# BigBoard.net
KiCad netlist of a schematic drawn in Altium Designer
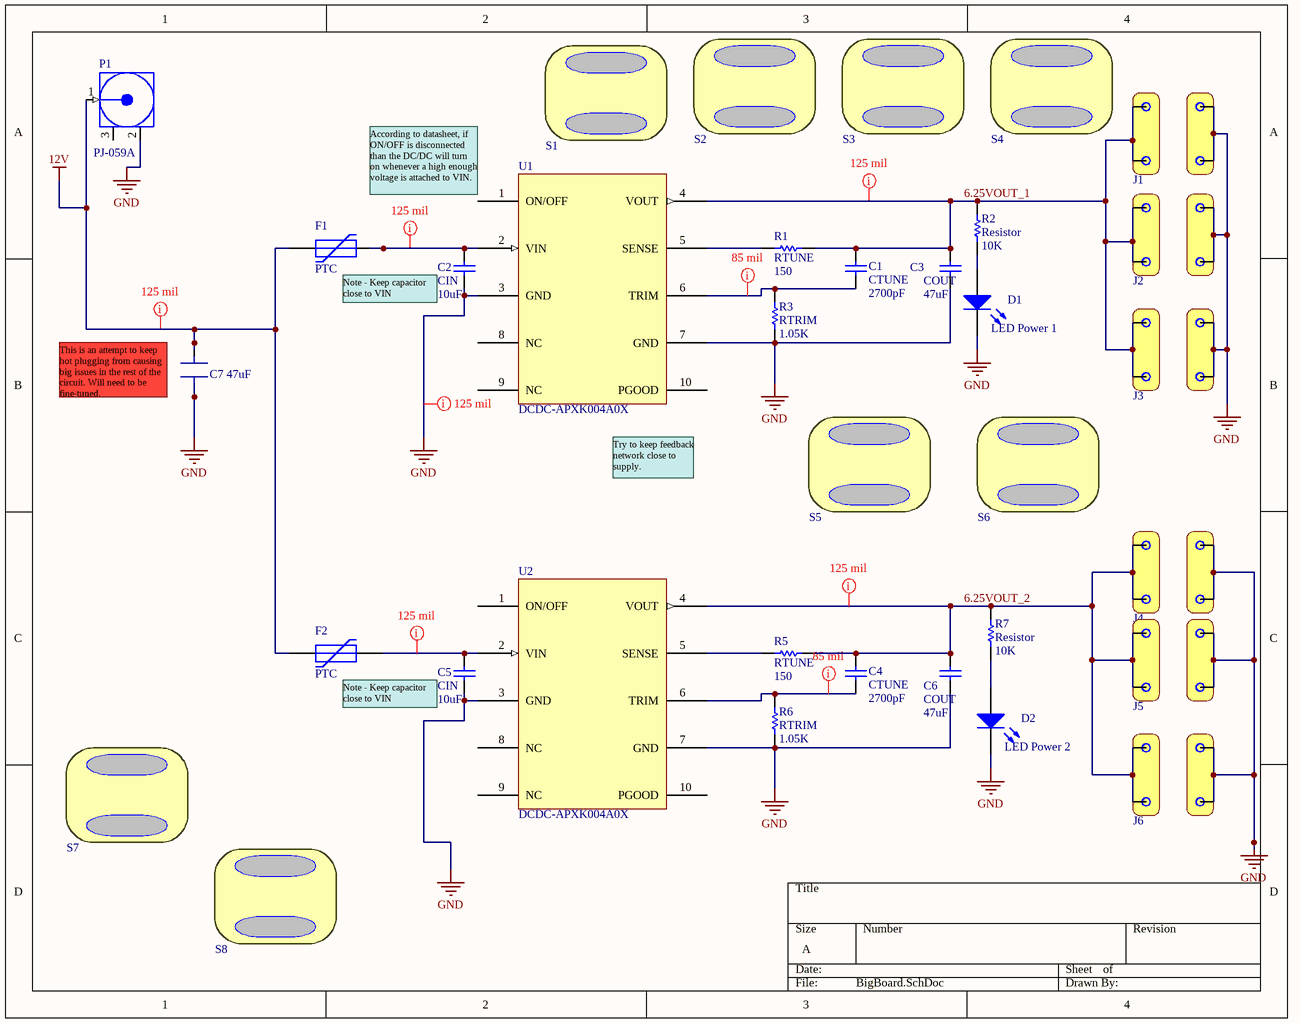
[diagram p0: BigBoard.SchDoc]

(export (version "E")
  (design (tool "Eeschema 10.0.6"))
  (components
    (comp (ref "C1")
      (value "CTUNE")
      (footprint "CAPC1608L")
      (description "Capacitor")
      (fields (field (name "ALTIUM_VALUE") "2700pF") (field (name "PUBLISHER") "Altium Limited"))
      (libsource (lib "mrone") (part "Cap"))
    )
    (comp (ref "C2")
      (value "CIN")
      (footprint "CAPC2012L")
      (description "Capacitor")
      (fields (field (name "ALTIUM_VALUE") "10uF") (field (name "PUBLISHER") "Altium Limited"))
      (libsource (lib "mrone") (part "Cap"))
    )
    (comp (ref "C3")
      (value "COUT")
      (footprint "CAPC3216L")
      (description "Capacitor")
      (fields (field (name "ALTIUM_VALUE") "47uF") (field (name "PUBLISHER") "Altium Limited"))
      (libsource (lib "mrone") (part "Cap"))
    )
    (comp (ref "C4")
      (value "CTUNE")
      (footprint "CAPC1608L")
      (description "Capacitor")
      (fields (field (name "ALTIUM_VALUE") "2700pF") (field (name "PUBLISHER") "Altium Limited"))
      (libsource (lib "mrone") (part "Cap"))
    )
    (comp (ref "C5")
      (value "CIN")
      (footprint "CAPC2012L")
      (description "Capacitor")
      (fields (field (name "ALTIUM_VALUE") "10uF") (field (name "PUBLISHER") "Altium Limited"))
      (libsource (lib "mrone") (part "Cap"))
    )
    (comp (ref "C6")
      (value "COUT")
      (footprint "CAPC3216L")
      (description "Capacitor")
      (fields (field (name "ALTIUM_VALUE") "47uF") (field (name "PUBLISHER") "Altium Limited"))
      (libsource (lib "mrone") (part "Cap"))
    )
    (comp (ref "C7 47uF")
      (value "CapTant6032-28")
      (footprint "CapTant6032-28")
      (description "Polarized Tantalum Capacitor for use in Toaster Charger")
      (libsource (lib "mrsl") (part "CapTant6032-28"))
    )
    (comp (ref "D1")
      (value "LED Power 1")
      (footprint "SurfaceMount(603)")
      (libsource (lib "mrone") (part "LED"))
    )
    (comp (ref "D2")
      (value "LED Power 2")
      (footprint "SurfaceMount(603)")
      (libsource (lib "mrone") (part "LED"))
    )
    (comp (ref "F1")
      (value "PTC")
      (footprint "J1-1812")
      (description "Fuse")
      (fields (field (name "PUBLISHER") "Altium Limited"))
      (libsource (lib "mrone") (part "PTC_FUSE"))
    )
    (comp (ref "F2")
      (value "PTC")
      (footprint "J1-1812")
      (description "Fuse")
      (fields (field (name "PUBLISHER") "Altium Limited"))
      (libsource (lib "mrone") (part "PTC_FUSE"))
    )
    (comp (ref "J1")
      (value "ToasterChargerProng")
      (footprint "ToasterChargerProng")
      (description "Charger Prong Footprint for Toaster Charger")
      (fields (field (name "PUBLISHER") "Altium Limited"))
      (libsource (lib "mrsl") (part "ToasterChargerProng"))
    )
    (comp (ref "J2")
      (value "ToasterChargerProng")
      (footprint "ToasterChargerProng")
      (description "Charger Prong Footprint for Toaster Charger")
      (fields (field (name "PUBLISHER") "Altium Limited"))
      (libsource (lib "mrsl") (part "ToasterChargerProng"))
    )
    (comp (ref "J3")
      (value "ToasterChargerProng")
      (footprint "ToasterChargerProng")
      (description "Charger Prong Footprint for Toaster Charger")
      (fields (field (name "PUBLISHER") "Altium Limited"))
      (libsource (lib "mrsl") (part "ToasterChargerProng"))
    )
    (comp (ref "J4")
      (value "ToasterChargerProng")
      (footprint "ToasterChargerProng")
      (description "Charger Prong Footprint for Toaster Charger")
      (fields (field (name "PUBLISHER") "Altium Limited"))
      (libsource (lib "mrsl") (part "ToasterChargerProng"))
    )
    (comp (ref "J5")
      (value "ToasterChargerProng")
      (footprint "ToasterChargerProng")
      (description "Charger Prong Footprint for Toaster Charger")
      (fields (field (name "PUBLISHER") "Altium Limited"))
      (libsource (lib "mrsl") (part "ToasterChargerProng"))
    )
    (comp (ref "J6")
      (value "ToasterChargerProng")
      (footprint "ToasterChargerProng")
      (description "Charger Prong Footprint for Toaster Charger")
      (fields (field (name "PUBLISHER") "Altium Limited"))
      (libsource (lib "mrsl") (part "ToasterChargerProng"))
    )
    (comp (ref "P1") (value "PJ-059A") (footprint "PJ-059A") (libsource (lib "mrsl") (part "PJ-059A")))
    (comp (ref "R1")
      (value "RTUNE")
      (footprint "J1-0603")
      (description "Resistor")
      (fields (field (name "ALTIUM_VALUE") "150") (field (name "PUBLISHER") "Altium Limited"))
      (libsource (lib "mrone") (part "Resistor"))
    )
    (comp (ref "R2")
      (value "Resistor")
      (footprint "J1-0603")
      (fields (field (name "ALTIUM_VALUE") "10K") (field (name "PUBLISHER") "Altium Limited"))
      (libsource (lib "mrone") (part "Resistor"))
    )
    (comp (ref "R3")
      (value "RTRIM")
      (footprint "J1-0603")
      (description "Resistor")
      (fields (field (name "ALTIUM_VALUE") "1.05K") (field (name "PUBLISHER") "Altium Limited"))
      (libsource (lib "mrone") (part "Resistor"))
    )
    (comp (ref "R5")
      (value "RTUNE")
      (footprint "J1-0603")
      (description "Resistor")
      (fields (field (name "ALTIUM_VALUE") "150") (field (name "PUBLISHER") "Altium Limited"))
      (libsource (lib "mrone") (part "Resistor"))
    )
    (comp (ref "R6")
      (value "RTRIM")
      (footprint "J1-0603")
      (description "Resistor")
      (fields (field (name "ALTIUM_VALUE") "1.05K") (field (name "PUBLISHER") "Altium Limited"))
      (libsource (lib "mrone") (part "Resistor"))
    )
    (comp (ref "R7")
      (value "Resistor")
      (footprint "J1-0603")
      (fields (field (name "ALTIUM_VALUE") "10K") (field (name "PUBLISHER") "Altium Limited"))
      (libsource (lib "mrone") (part "Resistor"))
    )
    (comp (ref "S1")
      (value "ToasterChargerZiptie")
      (footprint "TOASTERCHARGERZIPTIEREVISED2")
      (description "Slot for Ziptie connection between PCB and Toaster Charger")
      (libsource (lib "mrsl") (part "ToasterChargerZiptie"))
    )
    (comp (ref "S2")
      (value "ToasterChargerZiptie")
      (footprint "TOASTERCHARGERZIPTIEREVISED2")
      (description "Slot for Ziptie connection between PCB and Toaster Charger")
      (libsource (lib "mrsl") (part "ToasterChargerZiptie"))
    )
    (comp (ref "S3")
      (value "ToasterChargerZiptie")
      (footprint "TOASTERCHARGERZIPTIEREVISED2")
      (description "Slot for Ziptie connection between PCB and Toaster Charger")
      (libsource (lib "mrsl") (part "ToasterChargerZiptie"))
    )
    (comp (ref "S4")
      (value "ToasterChargerZiptie")
      (footprint "TOASTERCHARGERZIPTIEREVISED2")
      (description "Slot for Ziptie connection between PCB and Toaster Charger")
      (libsource (lib "mrsl") (part "ToasterChargerZiptie"))
    )
    (comp (ref "S5")
      (value "ToasterChargerZiptie")
      (footprint "TOASTERCHARGERZIPTIEREVISED2")
      (description "Slot for Ziptie connection between PCB and Toaster Charger")
      (libsource (lib "mrsl") (part "ToasterChargerZiptie"))
    )
    (comp (ref "S6")
      (value "ToasterChargerZiptie")
      (footprint "TOASTERCHARGERZIPTIEREVISED2")
      (description "Slot for Ziptie connection between PCB and Toaster Charger")
      (libsource (lib "mrsl") (part "ToasterChargerZiptie"))
    )
    (comp (ref "S7")
      (value "ToasterChargerZiptie")
      (footprint "TOASTERCHARGERZIPTIEREVISED2")
      (description "Slot for Ziptie connection between PCB and Toaster Charger")
      (libsource (lib "mrsl") (part "ToasterChargerZiptie"))
    )
    (comp (ref "S8")
      (value "ToasterChargerZiptie")
      (footprint "TOASTERCHARGERZIPTIEREVISED2")
      (description "Slot for Ziptie connection between PCB and Toaster Charger")
      (libsource (lib "mrsl") (part "ToasterChargerZiptie"))
    )
    (comp (ref "U1")
      (value "DCDC-APXK004A0X")
      (footprint "DCDC-APXK004A0X")
      (description "DC/DC converter for the rone charger")
      (libsource (lib "mrone") (part "DCDC-APXK004A0X"))
    )
    (comp (ref "U2")
      (value "DCDC-APXK004A0X")
      (footprint "DCDC-APXK004A0X")
      (description "DC/DC converter for the rone charger")
      (libsource (lib "mrone") (part "DCDC-APXK004A0X"))
    )
  )
  (nets
    (net (code "1") (name "/6.25VOUT_1") (class "Default")
      (node (ref "C1") (pin "1") (pinfunction "1_1") (pintype "passive"))
      (node (ref "C3") (pin "2") (pinfunction "2_2") (pintype "passive"))
      (node (ref "J1") (pin "1") (pinfunction "1_1") (pintype "passive"))
      (node (ref "J1") (pin "2") (pinfunction "2_2") (pintype "passive"))
      (node (ref "J2") (pin "1") (pinfunction "1_1") (pintype "passive"))
      (node (ref "J2") (pin "2") (pinfunction "2_2") (pintype "passive"))
      (node (ref "J3") (pin "1") (pinfunction "1_1") (pintype "passive"))
      (node (ref "J3") (pin "2") (pinfunction "2_2") (pintype "passive"))
      (node (ref "R1") (pin "1") (pinfunction "1_1") (pintype "passive"))
      (node (ref "R2") (pin "1") (pinfunction "1_1") (pintype "passive"))
      (node (ref "U1") (pin "4") (pinfunction "VOUT_4") (pintype "output"))
    )
    (net (code "2") (name "/6.25VOUT_2") (class "Default")
      (node (ref "C4") (pin "1") (pinfunction "1_1") (pintype "passive"))
      (node (ref "C6") (pin "2") (pinfunction "2_2") (pintype "passive"))
      (node (ref "J4") (pin "1") (pinfunction "1_1") (pintype "passive"))
      (node (ref "J4") (pin "2") (pinfunction "2_2") (pintype "passive"))
      (node (ref "J5") (pin "1") (pinfunction "1_1") (pintype "passive"))
      (node (ref "J5") (pin "2") (pinfunction "2_2") (pintype "passive"))
      (node (ref "J6") (pin "1") (pinfunction "1_1") (pintype "passive"))
      (node (ref "J6") (pin "2") (pinfunction "2_2") (pintype "passive"))
      (node (ref "R5") (pin "1") (pinfunction "1_1") (pintype "passive"))
      (node (ref "R7") (pin "1") (pinfunction "1_1") (pintype "passive"))
      (node (ref "U2") (pin "4") (pinfunction "VOUT_4") (pintype "output"))
    )
    (net (code "3") (name "12V") (class "Default")
      (node (ref "C7 47uF") (pin "1") (pintype "passive"))
      (node (ref "F1") (pin "1") (pinfunction "1_1") (pintype "passive"))
      (node (ref "F2") (pin "1") (pinfunction "1_1") (pintype "passive"))
      (node (ref "P1") (pin "1") (pinfunction "VCC_1") (pintype "input"))
    )
    (net (code "4") (name "GND") (class "Default")
      (node (ref "C2") (pin "1") (pinfunction "1_1") (pintype "passive"))
      (node (ref "C3") (pin "1") (pinfunction "1_1") (pintype "passive"))
      (node (ref "C5") (pin "1") (pinfunction "1_1") (pintype "passive"))
      (node (ref "C6") (pin "1") (pinfunction "1_1") (pintype "passive"))
      (node (ref "C7 47uF") (pin "2") (pintype "passive"))
      (node (ref "D1") (pin "2") (pinfunction "K_2") (pintype "passive"))
      (node (ref "D2") (pin "2") (pinfunction "K_2") (pintype "passive"))
      (node (ref "J1") (pin "3") (pinfunction "3_3") (pintype "passive"))
      (node (ref "J1") (pin "4") (pinfunction "4_4") (pintype "passive"))
      (node (ref "J2") (pin "3") (pinfunction "3_3") (pintype "passive"))
      (node (ref "J2") (pin "4") (pinfunction "4_4") (pintype "passive"))
      (node (ref "J3") (pin "3") (pinfunction "3_3") (pintype "passive"))
      (node (ref "J3") (pin "4") (pinfunction "4_4") (pintype "passive"))
      (node (ref "J4") (pin "3") (pinfunction "3_3") (pintype "passive"))
      (node (ref "J4") (pin "4") (pinfunction "4_4") (pintype "passive"))
      (node (ref "J5") (pin "3") (pinfunction "3_3") (pintype "passive"))
      (node (ref "J5") (pin "4") (pinfunction "4_4") (pintype "passive"))
      (node (ref "J6") (pin "3") (pinfunction "3_3") (pintype "passive"))
      (node (ref "J6") (pin "4") (pinfunction "4_4") (pintype "passive"))
      (node (ref "P1") (pin "2") (pinfunction "GND_2") (pintype "power_in"))
      (node (ref "R3") (pin "1") (pinfunction "1_1") (pintype "passive"))
      (node (ref "R6") (pin "1") (pinfunction "1_1") (pintype "passive"))
      (node (ref "U1") (pin "3") (pinfunction "GND_3") (pintype "power_in"))
      (node (ref "U1") (pin "7") (pinfunction "GND_7") (pintype "power_in"))
      (node (ref "U2") (pin "3") (pinfunction "GND_3") (pintype "power_in"))
      (node (ref "U2") (pin "7") (pinfunction "GND_7") (pintype "power_in"))
    )
    (net (code "5") (name "Net-(D1-A)") (class "Default")
      (node (ref "D1") (pin "1") (pinfunction "A_1") (pintype "passive"))
      (node (ref "R2") (pin "2") (pinfunction "2_2") (pintype "passive"))
    )
    (net (code "6") (name "Net-(D2-A)") (class "Default")
      (node (ref "D2") (pin "1") (pinfunction "A_1") (pintype "passive"))
      (node (ref "R7") (pin "2") (pinfunction "2_2") (pintype "passive"))
    )
    (net (code "7") (name "Net-(U1-SENSE)") (class "Default")
      (node (ref "R1") (pin "2") (pinfunction "2_2") (pintype "passive"))
      (node (ref "U1") (pin "5") (pinfunction "SENSE_5") (pintype "passive"))
    )
    (net (code "8") (name "Net-(U1-TRIM)") (class "Default")
      (node (ref "C1") (pin "2") (pinfunction "2_2") (pintype "passive"))
      (node (ref "R3") (pin "2") (pinfunction "2_2") (pintype "passive"))
      (node (ref "U1") (pin "6") (pinfunction "TRIM_6") (pintype "passive"))
    )
    (net (code "9") (name "Net-(U1-VIN)") (class "Default")
      (node (ref "C2") (pin "2") (pinfunction "2_2") (pintype "passive"))
      (node (ref "F1") (pin "2") (pinfunction "2_2") (pintype "passive"))
      (node (ref "U1") (pin "2") (pinfunction "VIN_2") (pintype "input"))
    )
    (net (code "10") (name "Net-(U2-SENSE)") (class "Default")
      (node (ref "R5") (pin "2") (pinfunction "2_2") (pintype "passive"))
      (node (ref "U2") (pin "5") (pinfunction "SENSE_5") (pintype "passive"))
    )
    (net (code "11") (name "Net-(U2-TRIM)") (class "Default")
      (node (ref "C4") (pin "2") (pinfunction "2_2") (pintype "passive"))
      (node (ref "R6") (pin "2") (pinfunction "2_2") (pintype "passive"))
      (node (ref "U2") (pin "6") (pinfunction "TRIM_6") (pintype "passive"))
    )
    (net (code "12") (name "Net-(U2-VIN)") (class "Default")
      (node (ref "C5") (pin "2") (pinfunction "2_2") (pintype "passive"))
      (node (ref "F2") (pin "2") (pinfunction "2_2") (pintype "passive"))
      (node (ref "U2") (pin "2") (pinfunction "VIN_2") (pintype "input"))
    )
    (net (code "13") (name "unconnected-(P1-Pad3)") (class "Default")
      (node (ref "P1") (pin "3") (pintype "passive"))
    )
    (net (code "14") (name "unconnected-(U1-NC-Pad8)") (class "Default")
      (node (ref "U1") (pin "8") (pinfunction "NC_8") (pintype "passive"))
    )
    (net (code "15") (name "unconnected-(U1-NC-Pad9)") (class "Default")
      (node (ref "U1") (pin "9") (pinfunction "NC_9") (pintype "passive"))
    )
    (net (code "16") (name "unconnected-(U1-ON{slash}OFF-Pad1)") (class "Default")
      (node (ref "U1") (pin "1") (pinfunction "ON/OFF_1") (pintype "power_in"))
    )
    (net (code "17") (name "unconnected-(U1-PGOOD-Pad10)") (class "Default")
      (node (ref "U1") (pin "10") (pinfunction "PGOOD_10") (pintype "passive"))
    )
    (net (code "18") (name "unconnected-(U2-NC-Pad8)") (class "Default")
      (node (ref "U2") (pin "8") (pinfunction "NC_8") (pintype "passive"))
    )
    (net (code "19") (name "unconnected-(U2-NC-Pad9)") (class "Default")
      (node (ref "U2") (pin "9") (pinfunction "NC_9") (pintype "passive"))
    )
    (net (code "20") (name "unconnected-(U2-ON{slash}OFF-Pad1)") (class "Default")
      (node (ref "U2") (pin "1") (pinfunction "ON/OFF_1") (pintype "power_in"))
    )
    (net (code "21") (name "unconnected-(U2-PGOOD-Pad10)") (class "Default")
      (node (ref "U2") (pin "10") (pinfunction "PGOOD_10") (pintype "passive"))
    )
  )
)
